# EDP_IronGenius_V3.net
KiCad netlist of a schematic drawn in Altium Designer
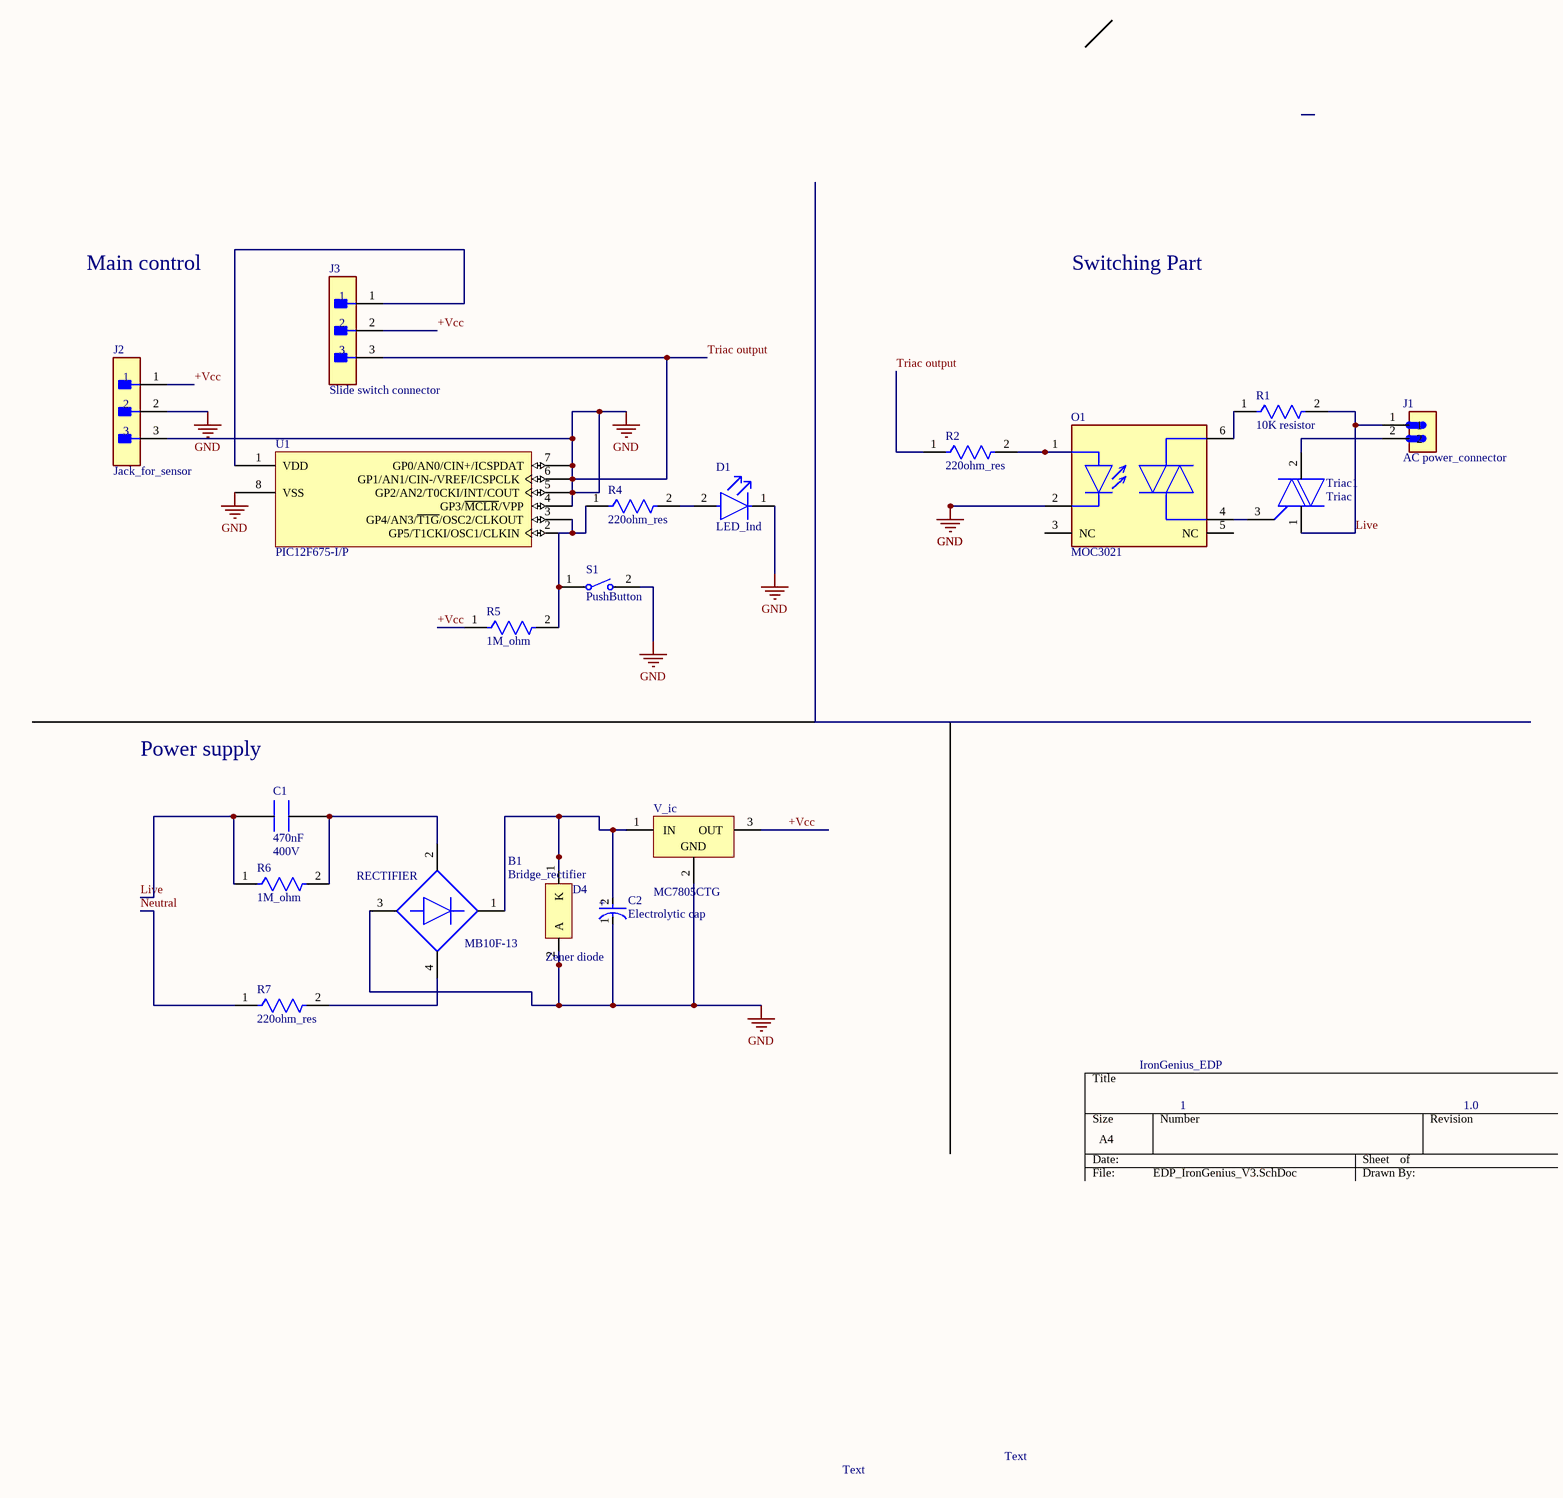
[diagram p0: EDP_IronGenius_V3.SchDoc]

(export (version "E")
  (design (tool "Eeschema 10.0.6"))
  (components
    (comp (ref "B1")
      (value "Bridge_rectifier")
      (footprint "Bridge rectifier")
      (description "Bridge Rectifier Diode, 1 Phase, 0.8A, 1000V V(RRM), Silicon")
      (fields
        (field (name "MANUFACTURER") "Diodes")
        (field (name "MANUFACTURER PART NUMBER") "MB10F-13")
        (field (name "DIODE TYPE") "RECTIFIER")
      )
      (libsource (lib "EDP_V3") (part "Bridge_rectifier"))
    )
    (comp (ref "C1")
      (value "470nF")
      (footprint "Capacitor 470nF 400V AC")
      (description "Film Capacitor, Polypropylene, 630V, 5% +Tol, 5% -Tol, 0.47uF, Through Hole Mount")
      (fields
        (field (name "MANUFACTURER") "KEMET")
        (field (name "MANUFACTURER PART NUMBER") "R76PR3470SE30J")
        (field (name "RATED AC VOLTAGE (URAC)") "400V")
      )
      (libsource (lib "EDP_v1") (part "Component_2"))
    )
    (comp (ref "C2")
      (value "Electrolytic cap")
      (footprint "Electrolytic cap")
      (fields
        (field (name "MANUFACTURER") "Panasonic")
        (field (name "MANUFACTURER PART NUMBER") "EEU-FR1H221B")
      )
      (libsource (lib "EDP_v1") (part "Electrolytic cap"))
    )
    (comp (ref "D1")
      (value "LED_Ind")
      (footprint "LED_ind")
      (description "Single Color LED, Yellow, Tinted Diffused, T-1, 3mm")
      (fields
        (field (name "MANUFACTURER") "Broadcom Avago")
        (field (name "MANUFACTURER PART NUMBER") "HLMP-1719")
      )
      (libsource (lib "EDP_v1") (part "LED_Ind"))
    )
    (comp (ref "D4")
      (value "Zener diode")
      (footprint "Diode")
      (description "Rectifier Diode, 1 Phase, 1 Element, 1A, 1000V V(RRM), Silicon, DO-41")
      (fields
        (field (name "MANUFACTURER") "ON Semiconductor")
        (field (name "MANUFACTURER PART NUMBER") "1N4007RLG")
      )
      (libsource (lib "EDP_v1") (part "Diode"))
    )
    (comp (ref "J1")
      (value "AC power_connector")
      (footprint "AC power_connector")
      (description "Barrier Strip Terminal Block, 10A, 1 Row(s), 1 Deck(s)")
      (fields
        (field (name "MANUFACTURER") "On-Shore Technology")
        (field (name "MANUFACTURER PART NUMBER") "OSTTE020104")
        (field (name "SAFETY APPROVAL") "UL,CUL")
      )
      (libsource (lib "EDP_v1") (part "AC power_connector"))
    )
    (comp (ref "J2")
      (value "Jack_for_sensor")
      (footprint "Sensor_jack")
      (description "Conn Shrouded Header (4 Sides) HDR 3 POS 2mm Solder RA Side Entry Thru-Hole Box")
      (fields
        (field (name "MANUFACTURER") "JST")
        (field (name "MANUFACTURER PART NUMBER") "S3B-PH-K-S(LF)(SN)")
      )
      (libsource (lib "EDP_v1") (part "Jack_for_sensor"))
    )
    (comp (ref "J3")
      (value "Slide switch connector")
      (footprint "Sensor_jack")
      (description "Conn Shrouded Header (4 Sides) HDR 3 POS 2mm Solder RA Side Entry Thru-Hole Box")
      (fields
        (field (name "MANUFACTURER") "JST")
        (field (name "MANUFACTURER PART NUMBER") "S3B-PH-K-S(LF)(SN)")
      )
      (libsource (lib "EDP_V3") (part "Jack_for_sensor"))
    )
    (comp (ref "O1")
      (value "MOC3021")
      (footprint "DIP6")
      (description "OPTOISOLATOR 4.17KV TRIAC 6DIP")
      (fields
        (field (name "MANUFACTURER") "ON Semiconductor / Fairchild")
        (field (name "MANUFACTURER PART NUMBER") "MOC3021M")
      )
      (libsource (lib "EDP_V3") (part "MOC3021"))
    )
    (comp (ref "R1")
      (value "10K resistor")
      (footprint "10K resistor")
      (description "Fixed Resistor, Thin Film, 0.6W, 1000ohm, 350V, 1% +/-Tol, 50ppm/Cel, Through Hole Mount")
      (fields
        (field (name "MANUFACTURER") "Vishay")
        (field (name "MANUFACTURER PART NUMBER") "MRS25000C1001FCT00")
      )
      (libsource (lib "EDP_v1") (part "10K resistor"))
    )
    (comp (ref "R2")
      (value "220ohm_res")
      (footprint "220ohm_res")
      (description "Fixed Resistor, Metal Film, 0.25W, 220ohm, 200V, 1% +/-Tol, 50ppm/Cel, Through Hole Mount")
      (fields
        (field (name "MANUFACTURER") "Vishay Beyschlag")
        (field (name "MANUFACTURER PART NUMBER") "MBA02040C2200FC100")
      )
      (libsource (lib "EDP_v1") (part "220ohm_res"))
    )
    (comp (ref "R4")
      (value "220ohm_res")
      (footprint "220ohm_res")
      (description "Fixed Resistor, Metal Film, 0.25W, 220ohm, 200V, 1% +/-Tol, 50ppm/Cel, Through Hole Mount")
      (fields
        (field (name "MANUFACTURER") "Vishay Beyschlag")
        (field (name "MANUFACTURER PART NUMBER") "MBA02040C2200FC100")
      )
      (libsource (lib "EDP_v1") (part "220ohm_res"))
    )
    (comp (ref "R5")
      (value "1M_ohm")
      (footprint "1M_om")
      (description "Fixed Resistor, Metal Film, 0.5W, 1000000ohm, 3500V, 1% +/-Tol, 200ppm/Cel, Through Hole Mount")
      (fields
        (field (name "MANUFACTURER") "Vishay BCcomponents")
        (field (name "MANUFACTURER PART NUMBER") "HVR3700001004FR500")
      )
      (libsource (lib "EDP_v1") (part "1M_ohm"))
    )
    (comp (ref "R6")
      (value "1M_ohm")
      (footprint "1M_om")
      (description "Fixed Resistor, Metal Film, 0.5W, 1000000ohm, 3500V, 1% +/-Tol, 200ppm/Cel, Through Hole Mount")
      (fields
        (field (name "MANUFACTURER") "Vishay BCcomponents")
        (field (name "MANUFACTURER PART NUMBER") "HVR3700001004FR500")
      )
      (libsource (lib "EDP_v1") (part "1M_ohm"))
    )
    (comp (ref "R7")
      (value "220ohm_res")
      (footprint "220ohm_res")
      (description "Fixed Resistor, Metal Film, 0.25W, 220ohm, 200V, 1% +/-Tol, 50ppm/Cel, Through Hole Mount")
      (fields
        (field (name "MANUFACTURER") "Vishay Beyschlag")
        (field (name "MANUFACTURER PART NUMBER") "MBA02040C2200FC100")
      )
      (libsource (lib "EDP_v1") (part "220ohm_res"))
    )
    (comp (ref "S1")
      (value "PushButton")
      (footprint "PushButton")
      (fields
        (field (name "MANUFACTURER") "TE Connectivity")
        (field (name "MANUFACTURER PART NUMBER") "2-1825910-7")
      )
      (libsource (lib "EDP_V3") (part "PushButton"))
    )
    (comp (ref "Triac1")
      (value "Triac")
      (footprint "Triac BTA16-600")
      (description "Snubberless TRIAC, 600V V(DRM), 16A I(T)RMS, TO-220AB")
      (fields
        (field (name "MANUFACTURER") "STMicroelectronics")
        (field (name "MANUFACTURER PART NUMBER") "BTA16-600CWRG")
      )
      (libsource (lib "EDP_v1") (part "Triac"))
    )
    (comp (ref "U1")
      (value "PIC12F675-I/P")
      (footprint "PDIP300-P8")
      (description "RISC Microcontroller, 8-Bit, FLASH, PIC CPU, 20MHz, CMOS, PDIP8")
      (fields (field (name "MANUFACTURER") "Microchip"))
      (libsource (lib "EDP_v1") (part "CMP-0190-00021-1"))
    )
    (comp (ref "V_ic")
      (value "MC7805CTG")
      (footprint "IC7805")
      (description "Fixed Positive Standard Regulator, 5VBIPolar")
      (fields (field (name "MANUFACTURER") "ON Semiconductor"))
      (libsource (lib "EDP_v1") (part "MC7805CTG"))
    )
  )
  (nets
    (net (code "1") (name "/+Vcc") (class "Default")
      (node (ref "J2") (pin "1") (pinfunction "1_1") (pintype "passive"))
      (node (ref "J3") (pin "2") (pinfunction "2_2") (pintype "passive"))
      (node (ref "R5") (pin "1") (pinfunction "1_1") (pintype "passive"))
      (node (ref "V_ic") (pin "3") (pinfunction "OUT_3") (pintype "power_in"))
    )
    (net (code "2") (name "/Live") (class "Default")
      (node (ref "C1") (pin "P10") (pinfunction "P10_P10") (pintype "passive"))
      (node (ref "J1") (pin "1") (pinfunction "1_1") (pintype "passive"))
      (node (ref "R1") (pin "2") (pinfunction "2_2") (pintype "passive"))
      (node (ref "R6") (pin "1") (pinfunction "1_1") (pintype "passive"))
      (node (ref "Triac1") (pin "1") (pinfunction "A1_1") (pintype "passive"))
    )
    (net (code "3") (name "/Neutral") (class "Default")
      (node (ref "R7") (pin "1") (pinfunction "1_1") (pintype "passive"))
    )
    (net (code "4") (name "GND") (class "Default")
      (node (ref "B1") (pin "3") (pinfunction "-_3") (pintype "passive"))
      (node (ref "C2") (pin "1") (pinfunction "C_1") (pintype "passive"))
      (node (ref "D1") (pin "1") (pinfunction "C_1") (pintype "passive"))
      (node (ref "D4") (pin "2") (pinfunction "A_2") (pintype "passive"))
      (node (ref "J2") (pin "2") (pinfunction "2_2") (pintype "passive"))
      (node (ref "J2") (pin "3") (pinfunction "3_3") (pintype "passive"))
      (node (ref "J3") (pin "3") (pinfunction "3_3") (pintype "passive"))
      (node (ref "O1") (pin "2") (pinfunction "C_2") (pintype "passive"))
      (node (ref "R2") (pin "1") (pinfunction "1_1") (pintype "passive"))
      (node (ref "S1") (pin "2") (pinfunction "2_2") (pintype "passive"))
      (node (ref "U1") (pin "4") (pinfunction "GP3/~{MCLR}/VPP_4") (pintype "bidirectional"))
      (node (ref "U1") (pin "5") (pinfunction "GP2/AN2/T0CKI/INT/COUT_5") (pintype "bidirectional"))
      (node (ref "U1") (pin "6") (pinfunction "GP1/AN1/CIN-/VREF/ICSPCLK_6") (pintype "bidirectional"))
      (node (ref "U1") (pin "7") (pinfunction "GP0/AN0/CIN+/ICSPDAT_7") (pintype "bidirectional"))
      (node (ref "U1") (pin "8") (pinfunction "VSS_8") (pintype "power_in"))
      (node (ref "V_ic") (pin "2") (pinfunction "GND_2") (pintype "power_in"))
    )
    (net (code "5") (name "Net-(B1-+)") (class "Default")
      (node (ref "B1") (pin "1") (pinfunction "+_1") (pintype "passive"))
      (node (ref "C2") (pin "2") (pinfunction "A_2") (pintype "passive"))
      (node (ref "D4") (pin "1") (pinfunction "K_1") (pintype "passive"))
      (node (ref "V_ic") (pin "1") (pinfunction "IN_1") (pintype "power_in"))
    )
    (net (code "6") (name "Net-(B1-1_~)") (class "Default")
      (node (ref "B1") (pin "2") (pinfunction "1_~_2") (pintype "passive"))
      (node (ref "C1") (pin "P9") (pinfunction "P9_P9") (pintype "passive"))
      (node (ref "R6") (pin "2") (pinfunction "2_2") (pintype "passive"))
    )
    (net (code "7") (name "Net-(B1-2_~)") (class "Default")
      (node (ref "B1") (pin "4") (pinfunction "2_~_4") (pintype "passive"))
      (node (ref "R7") (pin "2") (pinfunction "2_2") (pintype "passive"))
    )
    (net (code "8") (name "Net-(D1-A)") (class "Default")
      (node (ref "D1") (pin "2") (pinfunction "A_2") (pintype "passive"))
      (node (ref "R4") (pin "2") (pinfunction "2_2") (pintype "passive"))
    )
    (net (code "9") (name "Net-(O1-1_MAIN_TERM.)") (class "Default")
      (node (ref "O1") (pin "4") (pinfunction "1_MAIN_TERM._4") (pintype "passive"))
      (node (ref "Triac1") (pin "3") (pinfunction "G_3") (pintype "passive"))
    )
    (net (code "10") (name "Net-(O1-2_MAIN_TERM.)") (class "Default")
      (node (ref "O1") (pin "6") (pinfunction "2_MAIN_TERM._6") (pintype "passive"))
      (node (ref "R1") (pin "1") (pinfunction "1_1") (pintype "passive"))
    )
    (net (code "11") (name "Net-(O1-A)") (class "Default")
      (node (ref "O1") (pin "1") (pinfunction "A_1") (pintype "passive"))
      (node (ref "R2") (pin "2") (pinfunction "2_2") (pintype "passive"))
    )
    (net (code "12") (name "Net-(Triac1-A2)") (class "Default")
      (node (ref "J1") (pin "2") (pinfunction "2_2") (pintype "passive"))
      (node (ref "Triac1") (pin "2") (pinfunction "A2_2") (pintype "passive"))
    )
    (net (code "13") (name "Net-(U1-GP4{slash}AN3{slash}~{T1G}{slash}OSC2{slash}CLKOUT)") (class "Default")
      (node (ref "R4") (pin "1") (pinfunction "1_1") (pintype "passive"))
      (node (ref "R5") (pin "2") (pinfunction "2_2") (pintype "passive"))
      (node (ref "S1") (pin "1") (pinfunction "1_1") (pintype "passive"))
      (node (ref "U1") (pin "2") (pinfunction "GP5/T1CKI/OSC1/CLKIN_2") (pintype "bidirectional"))
      (node (ref "U1") (pin "3") (pinfunction "GP4/AN3/~{T1G}/OSC2/CLKOUT_3") (pintype "bidirectional"))
    )
    (net (code "14") (name "Net-(U1-VDD)") (class "Default")
      (node (ref "J3") (pin "1") (pinfunction "1_1") (pintype "passive"))
      (node (ref "U1") (pin "1") (pinfunction "VDD_1") (pintype "power_in"))
    )
    (net (code "15") (name "unconnected-(O1-NC-Pad3)") (class "Default")
      (node (ref "O1") (pin "3") (pinfunction "NC_3") (pintype "passive"))
    )
    (net (code "16") (name "unconnected-(O1-NC-Pad5)") (class "Default")
      (node (ref "O1") (pin "5") (pinfunction "NC_5") (pintype "passive"))
    )
  )
)
